# SEMAFORO.net
KiCad netlist of a schematic drawn in EAGLE
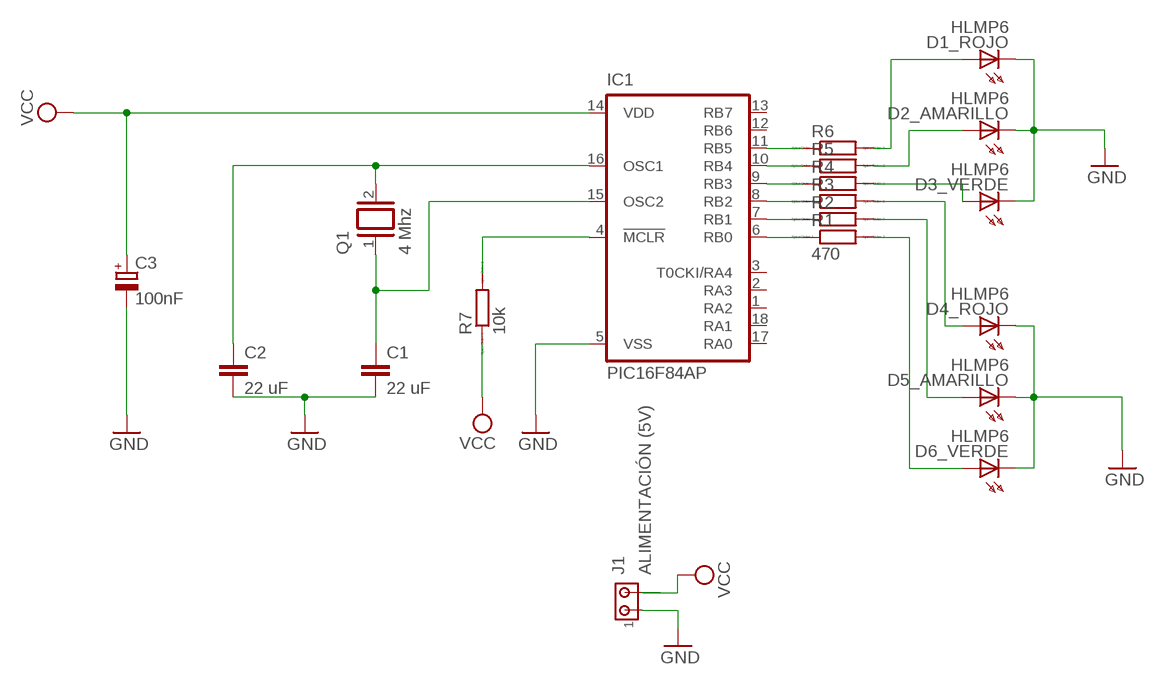
[diagram p0: schematic, sheet 1]

(export (version "E")
  (design (tool "Eeschema 10.0.6"))
  (components
    (comp (ref "C1")
      (value "22 uF")
      (footprint "eagle-import:C2.5-2")
      (libsource (lib "eagle-import") (part "C2.5/2"))
    )
    (comp (ref "C2")
      (value "22 uF")
      (footprint "eagle-import:C2.5-2")
      (libsource (lib "eagle-import") (part "C2.5/2"))
    )
    (comp (ref "C3")
      (value "100nF")
      (footprint "eagle-import:E1,8-4")
      (libsource (lib "eagle-import") (part "CPOL-EUE1.8-4"))
    )
    (comp (ref "D1_ROJO")
      (value "HLMP6")
      (footprint "eagle-import:HLMP6")
      (fields (field (name "MF") "AGILENT TECHNOLOGIES") (field (name "MPN") "HLMP-6500"))
      (libsource (lib "eagle-import") (part "HLMP6"))
    )
    (comp (ref "D2_AMARILLO")
      (value "HLMP6")
      (footprint "eagle-import:HLMP6")
      (fields (field (name "MF") "AGILENT TECHNOLOGIES") (field (name "MPN") "HLMP-6500"))
      (libsource (lib "eagle-import") (part "HLMP6"))
    )
    (comp (ref "D3_VERDE")
      (value "HLMP6")
      (footprint "eagle-import:HLMP6")
      (fields (field (name "MF") "AGILENT TECHNOLOGIES") (field (name "MPN") "HLMP-6500"))
      (libsource (lib "eagle-import") (part "HLMP6"))
    )
    (comp (ref "D4_ROJO")
      (value "HLMP6")
      (footprint "eagle-import:HLMP6")
      (fields (field (name "MF") "AGILENT TECHNOLOGIES") (field (name "MPN") "HLMP-6500"))
      (libsource (lib "eagle-import") (part "HLMP6"))
    )
    (comp (ref "D5_AMARILLO")
      (value "HLMP6")
      (footprint "eagle-import:HLMP6")
      (fields (field (name "MF") "AGILENT TECHNOLOGIES") (field (name "MPN") "HLMP-6500"))
      (libsource (lib "eagle-import") (part "HLMP6"))
    )
    (comp (ref "D6_VERDE")
      (value "HLMP6")
      (footprint "eagle-import:HLMP6")
      (fields (field (name "MF") "AGILENT TECHNOLOGIES") (field (name "MPN") "HLMP-6500"))
      (libsource (lib "eagle-import") (part "HLMP6"))
    )
    (comp (ref "IC1")
      (value "PIC16F84AP")
      (footprint "eagle-import:DIL18")
      (fields (field (name "MF") "MICROCHIP") (field (name "MPN") "PIC16F84A-04I/P"))
      (libsource (lib "eagle-import") (part "PIC16F8P4A"))
    )
    (comp (ref "J1")
      (value "ALIMENTACIÓN (5V)")
      (footprint "eagle-import:10X02MTA")
      (libsource (lib "eagle-import") (part "MTA02-100"))
    )
    (comp (ref "Q1")
      (value "4 Mhz")
      (footprint "eagle-import:QS")
      (libsource (lib "eagle-import") (part "XTAL/S"))
    )
    (comp (ref "R1")
      (value "470")
      (footprint "eagle-import:0207_10")
      (libsource (lib "eagle-import") (part "R0207/10"))
    )
    (comp (ref "R2")
      (value "R0207/10")
      (footprint "eagle-import:0207_10")
      (libsource (lib "eagle-import") (part "R0207/10"))
    )
    (comp (ref "R3")
      (value "R0207/10")
      (footprint "eagle-import:0207_10")
      (libsource (lib "eagle-import") (part "R0207/10"))
    )
    (comp (ref "R4")
      (value "R0207/10")
      (footprint "eagle-import:0207_10")
      (libsource (lib "eagle-import") (part "R0207/10"))
    )
    (comp (ref "R5")
      (value "R0207/10")
      (footprint "eagle-import:0207_10")
      (libsource (lib "eagle-import") (part "R0207/10"))
    )
    (comp (ref "R6")
      (value "R0207/10")
      (footprint "eagle-import:0207_10")
      (libsource (lib "eagle-import") (part "R0207/10"))
    )
    (comp (ref "R7")
      (value "10k")
      (footprint "eagle-import:0207_10")
      (libsource (lib "eagle-import") (part "R0207/10"))
    )
  )
  (nets
    (net (code "1") (name "GND") (class "Default")
      (node (ref "C1") (pin "2") (pinfunction "2_2") (pintype "passive"))
      (node (ref "C2") (pin "2") (pinfunction "2_2") (pintype "passive"))
      (node (ref "C3") (pin "-") (pinfunction "-_-") (pintype "passive"))
      (node (ref "D1_ROJO") (pin "K") (pinfunction "K_K") (pintype "passive"))
      (node (ref "D2_AMARILLO") (pin "K") (pinfunction "K_K") (pintype "passive"))
      (node (ref "D3_VERDE") (pin "K") (pinfunction "K_K") (pintype "passive"))
      (node (ref "D4_ROJO") (pin "K") (pinfunction "K_K") (pintype "passive"))
      (node (ref "D5_AMARILLO") (pin "K") (pinfunction "K_K") (pintype "passive"))
      (node (ref "D6_VERDE") (pin "K") (pinfunction "K_K") (pintype "passive"))
      (node (ref "IC1") (pin "5") (pinfunction "VSS_5") (pintype "power_in"))
      (node (ref "J1") (pin "1") (pinfunction "1_1") (pintype "passive"))
    )
    (net (code "2") (name "Net-(D1_ROJO-PadA)") (class "Default")
      (node (ref "D1_ROJO") (pin "A") (pinfunction "A_A") (pintype "passive"))
      (node (ref "R6") (pin "2") (pinfunction "2_2") (pintype "passive"))
    )
    (net (code "3") (name "Net-(D2_AMARILLO-PadA)") (class "Default")
      (node (ref "D2_AMARILLO") (pin "A") (pinfunction "A_A") (pintype "passive"))
      (node (ref "R5") (pin "2") (pinfunction "2_2") (pintype "passive"))
    )
    (net (code "4") (name "Net-(D3_VERDE-PadA)") (class "Default")
      (node (ref "D3_VERDE") (pin "A") (pinfunction "A_A") (pintype "passive"))
      (node (ref "R4") (pin "2") (pinfunction "2_2") (pintype "passive"))
    )
    (net (code "5") (name "Net-(D4_ROJO-PadA)") (class "Default")
      (node (ref "D4_ROJO") (pin "A") (pinfunction "A_A") (pintype "passive"))
      (node (ref "R3") (pin "2") (pinfunction "2_2") (pintype "passive"))
    )
    (net (code "6") (name "Net-(D5_AMARILLO-PadA)") (class "Default")
      (node (ref "D5_AMARILLO") (pin "A") (pinfunction "A_A") (pintype "passive"))
      (node (ref "R2") (pin "2") (pinfunction "2_2") (pintype "passive"))
    )
    (net (code "7") (name "Net-(D6_VERDE-PadA)") (class "Default")
      (node (ref "D6_VERDE") (pin "A") (pinfunction "A_A") (pintype "passive"))
      (node (ref "R1") (pin "2") (pinfunction "2_2") (pintype "passive"))
    )
    (net (code "8") (name "Net-(IC1-OSC1)") (class "Default")
      (node (ref "C2") (pin "1") (pinfunction "1_1") (pintype "passive"))
      (node (ref "IC1") (pin "16") (pinfunction "OSC1_16") (pintype "input"))
      (node (ref "Q1") (pin "2") (pinfunction "2_2") (pintype "passive"))
    )
    (net (code "9") (name "Net-(IC1-OSC2)") (class "Default")
      (node (ref "C1") (pin "1") (pinfunction "1_1") (pintype "passive"))
      (node (ref "IC1") (pin "15") (pinfunction "OSC2_15") (pintype "output"))
      (node (ref "Q1") (pin "1") (pinfunction "1_1") (pintype "passive"))
    )
    (net (code "10") (name "Net-(IC1-RB0)") (class "Default")
      (node (ref "IC1") (pin "6") (pinfunction "RB0_6") (pintype "bidirectional"))
      (node (ref "R1") (pin "1") (pinfunction "1_1") (pintype "passive"))
    )
    (net (code "11") (name "Net-(IC1-RB1)") (class "Default")
      (node (ref "IC1") (pin "7") (pinfunction "RB1_7") (pintype "bidirectional"))
      (node (ref "R2") (pin "1") (pinfunction "1_1") (pintype "passive"))
    )
    (net (code "12") (name "Net-(IC1-RB2)") (class "Default")
      (node (ref "IC1") (pin "8") (pinfunction "RB2_8") (pintype "bidirectional"))
      (node (ref "R3") (pin "1") (pinfunction "1_1") (pintype "passive"))
    )
    (net (code "13") (name "Net-(IC1-RB3)") (class "Default")
      (node (ref "IC1") (pin "9") (pinfunction "RB3_9") (pintype "bidirectional"))
      (node (ref "R4") (pin "1") (pinfunction "1_1") (pintype "passive"))
    )
    (net (code "14") (name "Net-(IC1-RB4)") (class "Default")
      (node (ref "IC1") (pin "10") (pinfunction "RB4_10") (pintype "bidirectional"))
      (node (ref "R5") (pin "1") (pinfunction "1_1") (pintype "passive"))
    )
    (net (code "15") (name "Net-(IC1-RB5)") (class "Default")
      (node (ref "IC1") (pin "11") (pinfunction "RB5_11") (pintype "bidirectional"))
      (node (ref "R6") (pin "1") (pinfunction "1_1") (pintype "passive"))
    )
    (net (code "16") (name "Net-(IC1-~{MCLR})") (class "Default")
      (node (ref "IC1") (pin "4") (pinfunction "~{MCLR}_4") (pintype "input"))
      (node (ref "R7") (pin "2") (pinfunction "2_2") (pintype "passive"))
    )
    (net (code "17") (name "VCC") (class "Default")
      (node (ref "C3") (pin "+") (pinfunction "+_+") (pintype "passive"))
      (node (ref "IC1") (pin "14") (pinfunction "VDD_14") (pintype "power_in"))
      (node (ref "J1") (pin "2") (pinfunction "2_2") (pintype "passive"))
      (node (ref "R7") (pin "1") (pinfunction "1_1") (pintype "passive"))
    )
    (net (code "18") (name "unconnected-(IC1-RA0-Pad17)") (class "Default")
      (node (ref "IC1") (pin "17") (pinfunction "RA0_17") (pintype "bidirectional"))
    )
    (net (code "19") (name "unconnected-(IC1-RA1-Pad18)") (class "Default")
      (node (ref "IC1") (pin "18") (pinfunction "RA1_18") (pintype "bidirectional"))
    )
    (net (code "20") (name "unconnected-(IC1-RA2-Pad1)") (class "Default")
      (node (ref "IC1") (pin "1") (pinfunction "RA2_1") (pintype "bidirectional"))
    )
    (net (code "21") (name "unconnected-(IC1-RA3-Pad2)") (class "Default")
      (node (ref "IC1") (pin "2") (pinfunction "RA3_2") (pintype "bidirectional"))
    )
    (net (code "22") (name "unconnected-(IC1-RB6-Pad12)") (class "Default")
      (node (ref "IC1") (pin "12") (pinfunction "RB6_12") (pintype "bidirectional"))
    )
    (net (code "23") (name "unconnected-(IC1-RB7-Pad13)") (class "Default")
      (node (ref "IC1") (pin "13") (pinfunction "RB7_13") (pintype "bidirectional"))
    )
    (net (code "24") (name "unconnected-(IC1-T0CKI{slash}RA4-Pad3)") (class "Default")
      (node (ref "IC1") (pin "3") (pinfunction "T0CKI/RA4_3") (pintype "bidirectional"))
    )
  )
)
